# LowVBoard_1_4.net
KiCad netlist of a schematic drawn in EAGLE
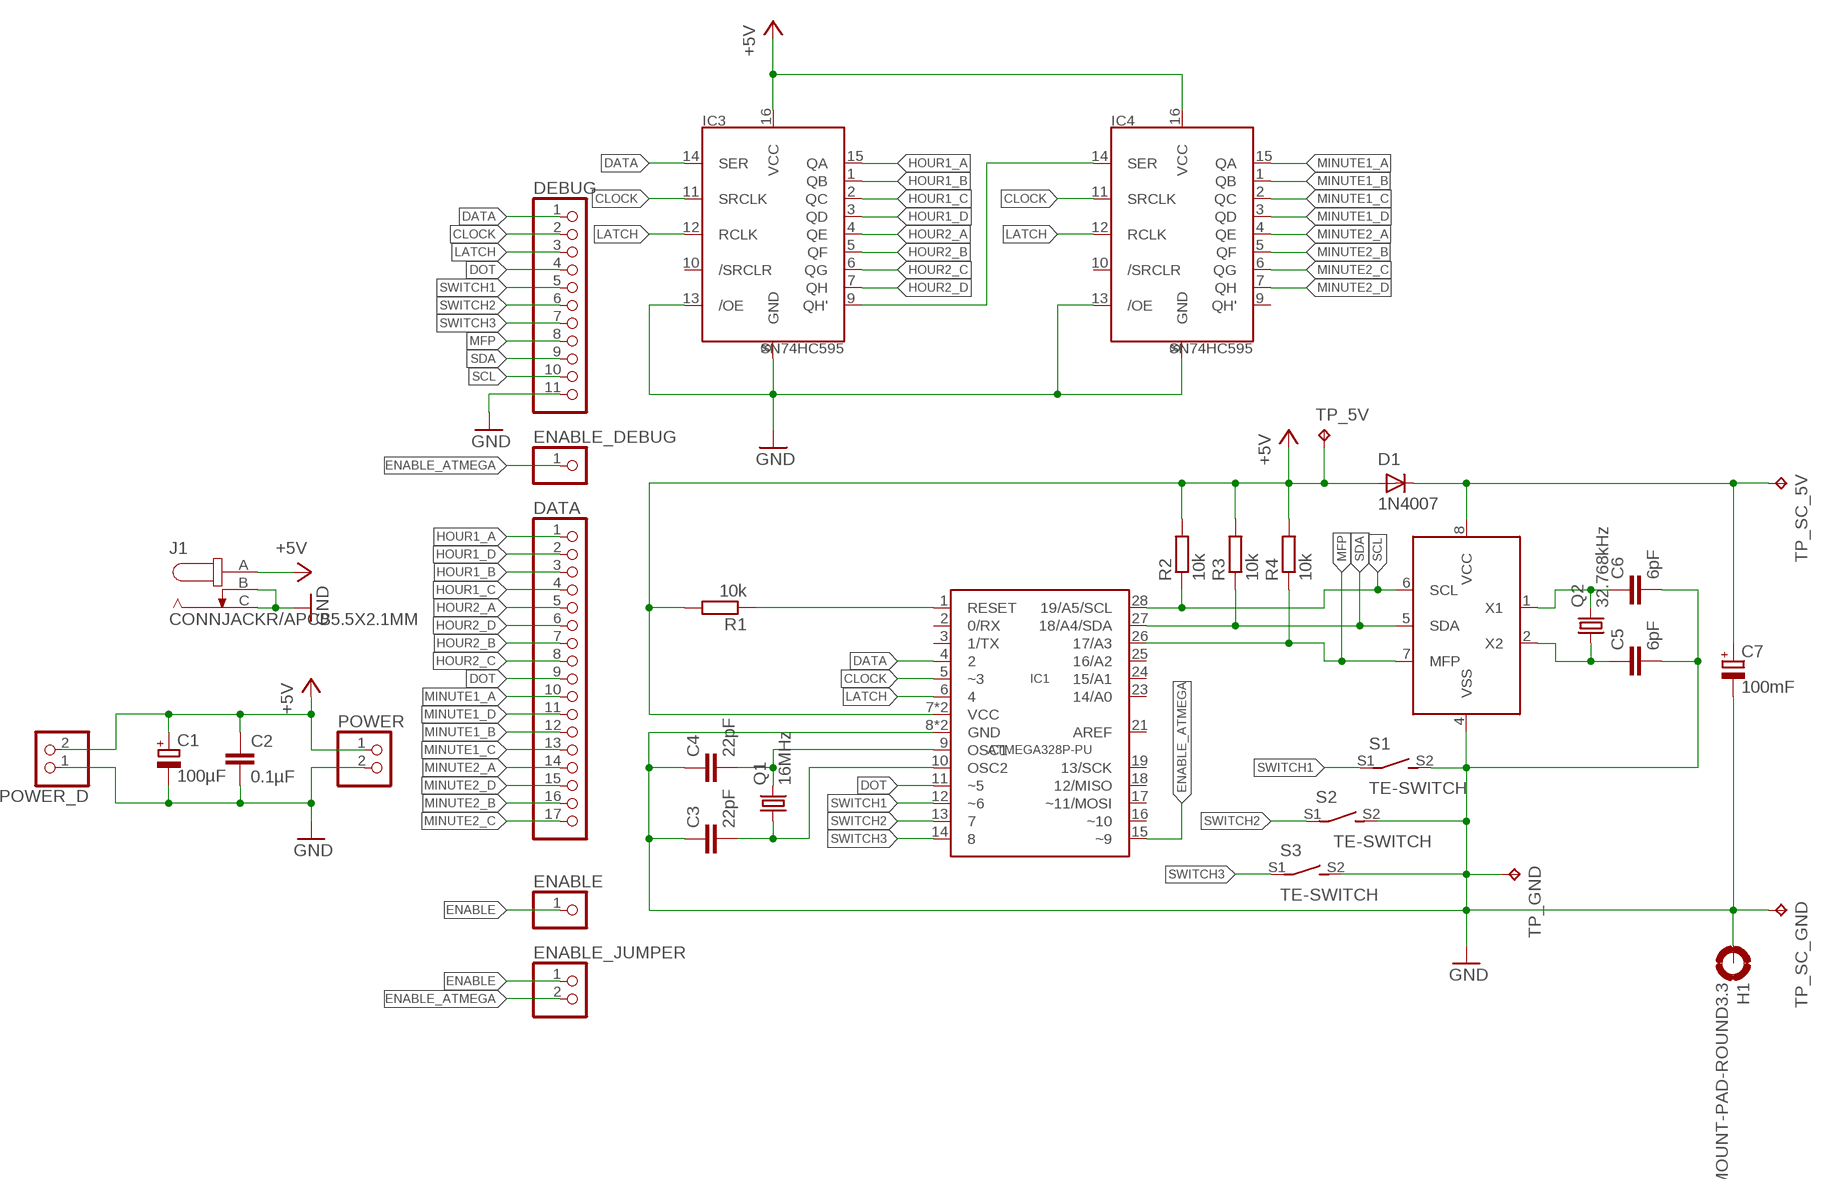
[diagram p0: schematic, sheet 1]

(export (version "E")
  (design (tool "Eeschema 10.0.6"))
  (components
    (comp (ref "C1")
      (value "100µF")
      (footprint "eagle-import:E2-5")
      (libsource (lib "eagle-import") (part "CPOL-EUE2-5"))
    )
    (comp (ref "C2")
      (value "0.1µF")
      (footprint "eagle-import:C025-024X044")
      (libsource (lib "eagle-import") (part "C-EU025-024X044"))
    )
    (comp (ref "C3")
      (value "22pF")
      (footprint "eagle-import:C025-024X044")
      (libsource (lib "eagle-import") (part "C-EU025-024X044"))
    )
    (comp (ref "C4")
      (value "22pF")
      (footprint "eagle-import:C025-024X044")
      (libsource (lib "eagle-import") (part "C-EU025-024X044"))
    )
    (comp (ref "C5")
      (value "6pF")
      (footprint "eagle-import:C025-024X044")
      (libsource (lib "eagle-import") (part "C-EU025-024X044"))
    )
    (comp (ref "C6")
      (value "6pF")
      (footprint "eagle-import:C025-024X044")
      (libsource (lib "eagle-import") (part "C-EU025-024X044"))
    )
    (comp (ref "C7")
      (value "100mF")
      (footprint "eagle-import:SUPERCAP-11.5")
      (libsource (lib "eagle-import") (part "FTW0H104ZF"))
    )
    (comp (ref "D1")
      (value "1N4007")
      (footprint "eagle-import:DO41-7.6")
      (libsource (lib "eagle-import") (part "1N4007"))
    )
    (comp (ref "DATA")
      (value "PINHD-1X17")
      (footprint "eagle-import:1X17")
      (libsource (lib "eagle-import") (part "PINHD-1X17"))
    )
    (comp (ref "DEBUG")
      (value "PINHD-1X11/90")
      (footprint "eagle-import:1X11_90")
      (libsource (lib "eagle-import") (part "PINHD-1X11/90"))
    )
    (comp (ref "ENABLE")
      (value "PINHD-1X1")
      (footprint "eagle-import:1X01")
      (libsource (lib "eagle-import") (part "PINHD-1X1"))
    )
    (comp (ref "ENABLE_DEBUG")
      (value "PINHD-1X1")
      (footprint "eagle-import:1X01")
      (libsource (lib "eagle-import") (part "PINHD-1X1"))
    )
    (comp (ref "ENABLE_JUMPER")
      (value "PINHD-1X2")
      (footprint "eagle-import:1X02")
      (libsource (lib "eagle-import") (part "PINHD-1X2"))
    )
    (comp (ref "H1")
      (value "MOUNT-PAD-ROUND3.3")
      (footprint "eagle-import:3,3-PAD")
      (libsource (lib "eagle-import") (part "MOUNT-PAD-ROUND3.3"))
    )
    (comp (ref "IC1")
      (value "ATMEGA328P-PU")
      (footprint "eagle-import:DIP28")
      (libsource (lib "eagle-import") (part "ATMEGA328P-PU"))
    )
    (comp (ref "IC2")
      (value "MCP7940M")
      (footprint "eagle-import:DIL8")
      (libsource (lib "eagle-import") (part "MCP7940M-I/P"))
    )
    (comp (ref "IC3")
      (value "SN74HC595")
      (footprint "eagle-import:DIL16")
      (libsource (lib "eagle-import") (part "SN74HC595"))
    )
    (comp (ref "IC4")
      (value "SN74HC595")
      (footprint "eagle-import:DIL16")
      (libsource (lib "eagle-import") (part "SN74HC595"))
    )
    (comp (ref "J1")
      (value "CONNJACKR/APCB5.5X2.1MM")
      (footprint "eagle-import:CONNJACKR_APCB5.5X2.1MM")
      (libsource (lib "eagle-import") (part "CONNJACKR/APCB5.5X2.1MM"))
    )
    (comp (ref "POWER")
      (value "PINHD-1X2")
      (footprint "eagle-import:1X02")
      (libsource (lib "eagle-import") (part "PINHD-1X2"))
    )
    (comp (ref "POWER_D")
      (value "PINHD-1X2/90")
      (footprint "eagle-import:1X02_90")
      (libsource (lib "eagle-import") (part "PINHD-1X2/90"))
    )
    (comp (ref "Q1")
      (value "16MHz")
      (footprint "eagle-import:HC49_S")
      (libsource (lib "eagle-import") (part "CRYSTALHC49S"))
    )
    (comp (ref "Q2")
      (value "32.768kHz")
      (footprint "eagle-import:CFS-206")
      (libsource (lib "eagle-import") (part "CFS-206"))
    )
    (comp (ref "R1")
      (value "10k")
      (footprint "eagle-import:0207_7")
      (libsource (lib "eagle-import") (part "R-EU_0207/7"))
    )
    (comp (ref "R2")
      (value "10k")
      (footprint "eagle-import:0207_7")
      (libsource (lib "eagle-import") (part "R-EU_0207/7"))
    )
    (comp (ref "R3")
      (value "10k")
      (footprint "eagle-import:0207_7")
      (libsource (lib "eagle-import") (part "R-EU_0207/7"))
    )
    (comp (ref "R4")
      (value "10k")
      (footprint "eagle-import:0207_7")
      (libsource (lib "eagle-import") (part "R-EU_0207/7"))
    )
    (comp (ref "S1")
      (value "TE-SWITCH")
      (footprint "eagle-import:TE-SWITCH")
      (libsource (lib "eagle-import") (part "TE-SWITCH"))
    )
    (comp (ref "S2")
      (value "TE-SWITCH")
      (footprint "eagle-import:TE-SWITCH")
      (libsource (lib "eagle-import") (part "TE-SWITCH"))
    )
    (comp (ref "S3")
      (value "TE-SWITCH")
      (footprint "eagle-import:TE-SWITCH")
      (libsource (lib "eagle-import") (part "TE-SWITCH"))
    )
    (comp (ref "TP_5V")
      (value "TPPAD1-13")
      (footprint "eagle-import:P1-13")
      (libsource (lib "eagle-import") (part "TPPAD1-13"))
    )
    (comp (ref "TP_GND")
      (value "TPPAD1-13")
      (footprint "eagle-import:P1-13")
      (libsource (lib "eagle-import") (part "TPPAD1-13"))
    )
    (comp (ref "TP_SC_5V")
      (value "TPPAD1-13")
      (footprint "eagle-import:P1-13")
      (libsource (lib "eagle-import") (part "TPPAD1-13"))
    )
    (comp (ref "TP_SC_GND")
      (value "TPPAD1-13")
      (footprint "eagle-import:P1-13")
      (libsource (lib "eagle-import") (part "TPPAD1-13"))
    )
  )
  (nets
    (net (code "1") (name "+5V") (class "Default")
      (node (ref "C1") (pin "+") (pinfunction "+_+") (pintype "passive"))
      (node (ref "C2") (pin "1") (pinfunction "1_1") (pintype "passive"))
      (node (ref "D1") (pin "A") (pinfunction "A_A") (pintype "passive"))
      (node (ref "IC1") (pin "20") (pinfunction "VCC_20") (pintype "bidirectional"))
      (node (ref "IC1") (pin "7") (pinfunction "VCC_7") (pintype "bidirectional"))
      (node (ref "IC3") (pin "16") (pinfunction "VCC_16") (pintype "bidirectional"))
      (node (ref "IC4") (pin "16") (pinfunction "VCC_16") (pintype "bidirectional"))
      (node (ref "J1") (pin "A") (pinfunction "A_A") (pintype "passive"))
      (node (ref "POWER") (pin "1") (pinfunction "1_1") (pintype "passive"))
      (node (ref "POWER_D") (pin "2") (pinfunction "2_2") (pintype "passive"))
      (node (ref "R1") (pin "2") (pinfunction "2_2") (pintype "passive"))
      (node (ref "R2") (pin "2") (pinfunction "2_2") (pintype "passive"))
      (node (ref "R3") (pin "2") (pinfunction "2_2") (pintype "passive"))
      (node (ref "R4") (pin "2") (pinfunction "2_2") (pintype "passive"))
      (node (ref "TP_5V") (pin "TP") (pinfunction "TP_TP") (pintype "input"))
    )
    (net (code "2") (name "CLOCK") (class "Default")
      (node (ref "DEBUG") (pin "2") (pinfunction "2_2") (pintype "passive"))
      (node (ref "IC1") (pin "5") (pinfunction "~{3}_5") (pintype "bidirectional"))
      (node (ref "IC3") (pin "11") (pinfunction "SRCLK_11") (pintype "bidirectional"))
      (node (ref "IC4") (pin "11") (pinfunction "SRCLK_11") (pintype "bidirectional"))
    )
    (net (code "3") (name "DATA") (class "Default")
      (node (ref "DEBUG") (pin "1") (pinfunction "1_1") (pintype "passive"))
      (node (ref "IC1") (pin "4") (pinfunction "2_4") (pintype "bidirectional"))
      (node (ref "IC3") (pin "14") (pinfunction "SER_14") (pintype "bidirectional"))
    )
    (net (code "4") (name "DOT") (class "Default")
      (node (ref "DATA") (pin "9") (pinfunction "9_9") (pintype "passive"))
      (node (ref "DEBUG") (pin "4") (pinfunction "4_4") (pintype "passive"))
      (node (ref "IC1") (pin "11") (pinfunction "~{5}_11") (pintype "bidirectional"))
    )
    (net (code "5") (name "ENABLE") (class "Default")
      (node (ref "ENABLE") (pin "1") (pinfunction "1_1") (pintype "passive"))
      (node (ref "ENABLE_JUMPER") (pin "1") (pinfunction "1_1") (pintype "passive"))
    )
    (net (code "6") (name "ENABLE_ATMEGA") (class "Default")
      (node (ref "ENABLE_DEBUG") (pin "1") (pinfunction "1_1") (pintype "passive"))
      (node (ref "ENABLE_JUMPER") (pin "2") (pinfunction "2_2") (pintype "passive"))
      (node (ref "IC1") (pin "15") (pinfunction "~{9}_15") (pintype "bidirectional"))
    )
    (net (code "7") (name "GND") (class "Default")
      (node (ref "C1") (pin "-") (pinfunction "-_-") (pintype "passive"))
      (node (ref "C2") (pin "2") (pinfunction "2_2") (pintype "passive"))
      (node (ref "C3") (pin "1") (pinfunction "1_1") (pintype "passive"))
      (node (ref "C4") (pin "1") (pinfunction "1_1") (pintype "passive"))
      (node (ref "C5") (pin "2") (pinfunction "2_2") (pintype "passive"))
      (node (ref "C6") (pin "2") (pinfunction "2_2") (pintype "passive"))
      (node (ref "C7") (pin "-") (pinfunction "-_-") (pintype "passive"))
      (node (ref "DEBUG") (pin "11") (pinfunction "11_11") (pintype "passive"))
      (node (ref "H1") (pin "B3,3") (pinfunction "MOUNT_B3,3") (pintype "passive"))
      (node (ref "IC1") (pin "22") (pinfunction "GND_22") (pintype "bidirectional"))
      (node (ref "IC1") (pin "8") (pinfunction "GND_8") (pintype "bidirectional"))
      (node (ref "IC2") (pin "4") (pinfunction "VSS_4") (pintype "bidirectional"))
      (node (ref "IC3") (pin "13") (pinfunction "/OE_13") (pintype "bidirectional"))
      (node (ref "IC3") (pin "8") (pinfunction "GND_8") (pintype "bidirectional"))
      (node (ref "IC4") (pin "13") (pinfunction "/OE_13") (pintype "bidirectional"))
      (node (ref "IC4") (pin "8") (pinfunction "GND_8") (pintype "bidirectional"))
      (node (ref "J1") (pin "B") (pinfunction "B_B") (pintype "passive"))
      (node (ref "J1") (pin "C") (pinfunction "C_C") (pintype "passive"))
      (node (ref "POWER") (pin "2") (pinfunction "2_2") (pintype "passive"))
      (node (ref "POWER_D") (pin "1") (pinfunction "1_1") (pintype "passive"))
      (node (ref "S1") (pin "S2") (pinfunction "S_S2") (pintype "passive"))
      (node (ref "S2") (pin "S2") (pinfunction "S_S2") (pintype "passive"))
      (node (ref "S3") (pin "S2") (pinfunction "S_S2") (pintype "passive"))
      (node (ref "TP_GND") (pin "TP") (pinfunction "TP_TP") (pintype "input"))
      (node (ref "TP_SC_GND") (pin "TP") (pinfunction "TP_TP") (pintype "input"))
    )
    (net (code "8") (name "HOUR1_A") (class "Default")
      (node (ref "DATA") (pin "1") (pinfunction "1_1") (pintype "passive"))
      (node (ref "IC3") (pin "15") (pinfunction "QA_15") (pintype "bidirectional"))
    )
    (net (code "9") (name "HOUR1_B") (class "Default")
      (node (ref "DATA") (pin "3") (pinfunction "3_3") (pintype "passive"))
      (node (ref "IC3") (pin "1") (pinfunction "QB_1") (pintype "bidirectional"))
    )
    (net (code "10") (name "HOUR1_C") (class "Default")
      (node (ref "DATA") (pin "4") (pinfunction "4_4") (pintype "passive"))
      (node (ref "IC3") (pin "2") (pinfunction "QC_2") (pintype "bidirectional"))
    )
    (net (code "11") (name "HOUR1_D") (class "Default")
      (node (ref "DATA") (pin "2") (pinfunction "2_2") (pintype "passive"))
      (node (ref "IC3") (pin "3") (pinfunction "QD_3") (pintype "bidirectional"))
    )
    (net (code "12") (name "HOUR2_A") (class "Default")
      (node (ref "DATA") (pin "5") (pinfunction "5_5") (pintype "passive"))
      (node (ref "IC3") (pin "4") (pinfunction "QE_4") (pintype "bidirectional"))
    )
    (net (code "13") (name "HOUR2_B") (class "Default")
      (node (ref "DATA") (pin "7") (pinfunction "7_7") (pintype "passive"))
      (node (ref "IC3") (pin "5") (pinfunction "QF_5") (pintype "bidirectional"))
    )
    (net (code "14") (name "HOUR2_C") (class "Default")
      (node (ref "DATA") (pin "8") (pinfunction "8_8") (pintype "passive"))
      (node (ref "IC3") (pin "6") (pinfunction "QG_6") (pintype "bidirectional"))
    )
    (net (code "15") (name "HOUR2_D") (class "Default")
      (node (ref "DATA") (pin "6") (pinfunction "6_6") (pintype "passive"))
      (node (ref "IC3") (pin "7") (pinfunction "QH_7") (pintype "bidirectional"))
    )
    (net (code "16") (name "LATCH") (class "Default")
      (node (ref "DEBUG") (pin "3") (pinfunction "3_3") (pintype "passive"))
      (node (ref "IC1") (pin "6") (pinfunction "4_6") (pintype "bidirectional"))
      (node (ref "IC3") (pin "12") (pinfunction "RCLK_12") (pintype "bidirectional"))
      (node (ref "IC4") (pin "12") (pinfunction "RCLK_12") (pintype "bidirectional"))
    )
    (net (code "17") (name "MFP") (class "Default")
      (node (ref "DEBUG") (pin "8") (pinfunction "8_8") (pintype "passive"))
      (node (ref "IC1") (pin "26") (pinfunction "17/A3_26") (pintype "bidirectional"))
      (node (ref "IC2") (pin "7") (pinfunction "MFP_7") (pintype "bidirectional"))
      (node (ref "R4") (pin "1") (pinfunction "1_1") (pintype "passive"))
    )
    (net (code "18") (name "MINUTE1_A") (class "Default")
      (node (ref "DATA") (pin "10") (pinfunction "10_10") (pintype "passive"))
      (node (ref "IC4") (pin "15") (pinfunction "QA_15") (pintype "bidirectional"))
    )
    (net (code "19") (name "MINUTE1_B") (class "Default")
      (node (ref "DATA") (pin "12") (pinfunction "12_12") (pintype "passive"))
      (node (ref "IC4") (pin "1") (pinfunction "QB_1") (pintype "bidirectional"))
    )
    (net (code "20") (name "MINUTE1_C") (class "Default")
      (node (ref "DATA") (pin "13") (pinfunction "13_13") (pintype "passive"))
      (node (ref "IC4") (pin "2") (pinfunction "QC_2") (pintype "bidirectional"))
    )
    (net (code "21") (name "MINUTE1_D") (class "Default")
      (node (ref "DATA") (pin "11") (pinfunction "11_11") (pintype "passive"))
      (node (ref "IC4") (pin "3") (pinfunction "QD_3") (pintype "bidirectional"))
    )
    (net (code "22") (name "MINUTE2_A") (class "Default")
      (node (ref "DATA") (pin "14") (pinfunction "14_14") (pintype "passive"))
      (node (ref "IC4") (pin "4") (pinfunction "QE_4") (pintype "bidirectional"))
    )
    (net (code "23") (name "MINUTE2_B") (class "Default")
      (node (ref "DATA") (pin "16") (pinfunction "16_16") (pintype "passive"))
      (node (ref "IC4") (pin "5") (pinfunction "QF_5") (pintype "bidirectional"))
    )
    (net (code "24") (name "MINUTE2_C") (class "Default")
      (node (ref "DATA") (pin "17") (pinfunction "17_17") (pintype "passive"))
      (node (ref "IC4") (pin "6") (pinfunction "QG_6") (pintype "bidirectional"))
    )
    (net (code "25") (name "MINUTE2_D") (class "Default")
      (node (ref "DATA") (pin "15") (pinfunction "15_15") (pintype "passive"))
      (node (ref "IC4") (pin "7") (pinfunction "QH_7") (pintype "bidirectional"))
    )
    (net (code "26") (name "Net-(IC1-OSC1)") (class "Default")
      (node (ref "C4") (pin "2") (pinfunction "2_2") (pintype "passive"))
      (node (ref "IC1") (pin "9") (pinfunction "OSC1_9") (pintype "bidirectional"))
      (node (ref "Q1") (pin "2") (pinfunction "2_2") (pintype "passive"))
    )
    (net (code "27") (name "Net-(IC1-OSC2)") (class "Default")
      (node (ref "C3") (pin "2") (pinfunction "2_2") (pintype "passive"))
      (node (ref "IC1") (pin "10") (pinfunction "OSC2_10") (pintype "bidirectional"))
      (node (ref "Q1") (pin "1") (pinfunction "1_1") (pintype "passive"))
    )
    (net (code "28") (name "Net-(IC1-RESET)") (class "Default")
      (node (ref "IC1") (pin "1") (pinfunction "RESET_1") (pintype "bidirectional"))
      (node (ref "R1") (pin "1") (pinfunction "1_1") (pintype "passive"))
    )
    (net (code "29") (name "Net-(IC2-VCC)") (class "Default")
      (node (ref "C7") (pin "+") (pinfunction "+_+") (pintype "passive"))
      (node (ref "D1") (pin "C") (pinfunction "C_C") (pintype "passive"))
      (node (ref "IC2") (pin "8") (pinfunction "VCC_8") (pintype "bidirectional"))
      (node (ref "TP_SC_5V") (pin "TP") (pinfunction "TP_TP") (pintype "input"))
    )
    (net (code "30") (name "Net-(IC2-X1)") (class "Default")
      (node (ref "C6") (pin "1") (pinfunction "1_1") (pintype "passive"))
      (node (ref "IC2") (pin "1") (pinfunction "X1_1") (pintype "bidirectional"))
      (node (ref "Q2") (pin "P$2") (pinfunction "2_P$2") (pintype "passive"))
    )
    (net (code "31") (name "Net-(IC2-X2)") (class "Default")
      (node (ref "C5") (pin "1") (pinfunction "1_1") (pintype "passive"))
      (node (ref "IC2") (pin "2") (pinfunction "X2_2") (pintype "bidirectional"))
      (node (ref "Q2") (pin "P$1") (pinfunction "1_P$1") (pintype "passive"))
    )
    (net (code "32") (name "Net-(IC3-QH')") (class "Default")
      (node (ref "IC3") (pin "9") (pinfunction "QH'_9") (pintype "bidirectional"))
      (node (ref "IC4") (pin "14") (pinfunction "SER_14") (pintype "bidirectional"))
    )
    (net (code "33") (name "SCL") (class "Default")
      (node (ref "DEBUG") (pin "10") (pinfunction "10_10") (pintype "passive"))
      (node (ref "IC1") (pin "28") (pinfunction "19/A5/SCL_28") (pintype "bidirectional"))
      (node (ref "IC2") (pin "6") (pinfunction "SCL_6") (pintype "bidirectional"))
      (node (ref "R2") (pin "1") (pinfunction "1_1") (pintype "passive"))
    )
    (net (code "34") (name "SDA") (class "Default")
      (node (ref "DEBUG") (pin "9") (pinfunction "9_9") (pintype "passive"))
      (node (ref "IC1") (pin "27") (pinfunction "18/A4/SDA_27") (pintype "bidirectional"))
      (node (ref "IC2") (pin "5") (pinfunction "SDA_5") (pintype "bidirectional"))
      (node (ref "R3") (pin "1") (pinfunction "1_1") (pintype "passive"))
    )
    (net (code "35") (name "SWITCH1") (class "Default")
      (node (ref "DEBUG") (pin "5") (pinfunction "5_5") (pintype "passive"))
      (node (ref "IC1") (pin "12") (pinfunction "~{6}_12") (pintype "bidirectional"))
      (node (ref "S1") (pin "S1") (pinfunction "P_S1") (pintype "passive"))
    )
    (net (code "36") (name "SWITCH2") (class "Default")
      (node (ref "DEBUG") (pin "6") (pinfunction "6_6") (pintype "passive"))
      (node (ref "IC1") (pin "13") (pinfunction "7_13") (pintype "bidirectional"))
      (node (ref "S2") (pin "S1") (pinfunction "P_S1") (pintype "passive"))
    )
    (net (code "37") (name "SWITCH3") (class "Default")
      (node (ref "DEBUG") (pin "7") (pinfunction "7_7") (pintype "passive"))
      (node (ref "IC1") (pin "14") (pinfunction "8_14") (pintype "bidirectional"))
      (node (ref "S3") (pin "S1") (pinfunction "P_S1") (pintype "passive"))
    )
    (net (code "38") (name "unconnected-(IC1-0{slash}RX-Pad2)") (class "Default")
      (node (ref "IC1") (pin "2") (pinfunction "0/RX_2") (pintype "bidirectional"))
    )
    (net (code "39") (name "unconnected-(IC1-1{slash}TX-Pad3)") (class "Default")
      (node (ref "IC1") (pin "3") (pinfunction "1/TX_3") (pintype "bidirectional"))
    )
    (net (code "40") (name "unconnected-(IC1-12{slash}MISO-Pad18)") (class "Default")
      (node (ref "IC1") (pin "18") (pinfunction "12/MISO_18") (pintype "bidirectional"))
    )
    (net (code "41") (name "unconnected-(IC1-13{slash}SCK-Pad19)") (class "Default")
      (node (ref "IC1") (pin "19") (pinfunction "13/SCK_19") (pintype "bidirectional"))
    )
    (net (code "42") (name "unconnected-(IC1-14{slash}A0-Pad23)") (class "Default")
      (node (ref "IC1") (pin "23") (pinfunction "14/A0_23") (pintype "bidirectional"))
    )
    (net (code "43") (name "unconnected-(IC1-15{slash}A1-Pad24)") (class "Default")
      (node (ref "IC1") (pin "24") (pinfunction "15/A1_24") (pintype "bidirectional"))
    )
    (net (code "44") (name "unconnected-(IC1-16{slash}A2-Pad25)") (class "Default")
      (node (ref "IC1") (pin "25") (pinfunction "16/A2_25") (pintype "bidirectional"))
    )
    (net (code "45") (name "unconnected-(IC1-AREF-Pad21)") (class "Default")
      (node (ref "IC1") (pin "21") (pinfunction "AREF_21") (pintype "bidirectional"))
    )
    (net (code "46") (name "unconnected-(IC1-~{10}-Pad16)") (class "Default")
      (node (ref "IC1") (pin "16") (pinfunction "~{10}_16") (pintype "bidirectional"))
    )
    (net (code "47") (name "unconnected-(IC1-~{11{slash}MOSI}-Pad17)") (class "Default")
      (node (ref "IC1") (pin "17") (pinfunction "~{11/MOSI}_17") (pintype "bidirectional"))
    )
    (net (code "48") (name "unconnected-(IC3-{slash}SRCLR-Pad10)") (class "Default")
      (node (ref "IC3") (pin "10") (pinfunction "/SRCLR_10") (pintype "bidirectional"))
    )
    (net (code "49") (name "unconnected-(IC4-QH'-Pad9)") (class "Default")
      (node (ref "IC4") (pin "9") (pinfunction "QH'_9") (pintype "bidirectional"))
    )
    (net (code "50") (name "unconnected-(IC4-{slash}SRCLR-Pad10)") (class "Default")
      (node (ref "IC4") (pin "10") (pinfunction "/SRCLR_10") (pintype "bidirectional"))
    )
  )
)
